# sb-mote2-oblong.net
KiCad netlist of a schematic drawn in EAGLE
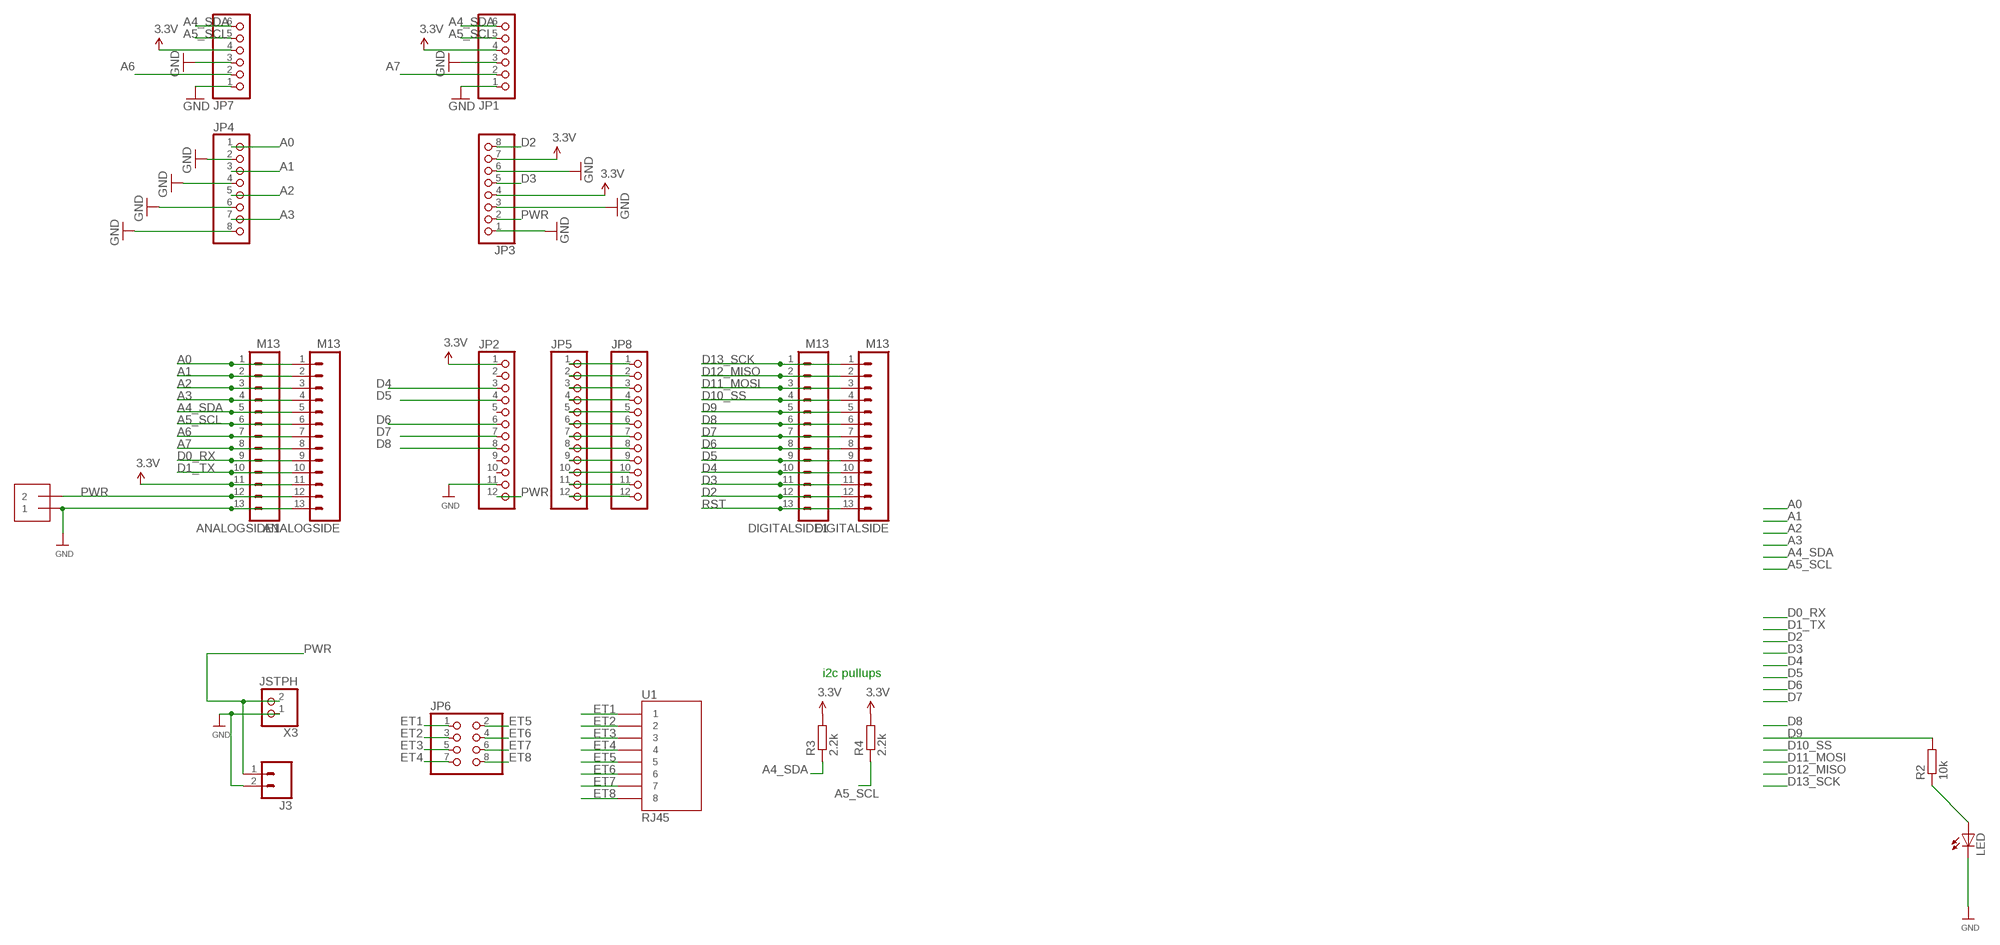
[diagram p0: schematic, sheet 1]

(export (version "E")
  (design (tool "Eeschema 10.0.6"))
  (components
    (comp (ref "ANALOGSIDE")
      (value "M13")
      (footprint "eagle-import:1X13")
      (libsource (lib "eagle-import") (part "M13"))
    )
    (comp (ref "ANALOGSIDE1")
      (value "M13")
      (footprint "eagle-import:1X13")
      (libsource (lib "eagle-import") (part "M13"))
    )
    (comp (ref "DIGITALSIDE")
      (value "M13")
      (footprint "eagle-import:1X13")
      (libsource (lib "eagle-import") (part "M13"))
    )
    (comp (ref "DIGITALSIDE1")
      (value "M13")
      (footprint "eagle-import:1X13")
      (libsource (lib "eagle-import") (part "M13"))
    )
    (comp (ref "J2")
      (value "1X2-3.5MM")
      (footprint "eagle-import:1X2-3.5MM")
      (libsource (lib "eagle-import") (part "1X2-3.5MM"))
    )
    (comp (ref "J3")
      (value "M02PTH")
      (footprint "eagle-import:1X02")
      (libsource (lib "eagle-import") (part "M02PTH"))
    )
    (comp (ref "JP1")
      (value "PINHD-1X6-3.5MM")
      (footprint "eagle-import:1X06-3.5MM")
      (libsource (lib "eagle-import") (part "PINHD-1X6-3.5MM"))
    )
    (comp (ref "JP2")
      (value "PINHD-1X12-CB")
      (footprint "eagle-import:1X12-CB")
      (libsource (lib "eagle-import") (part "PINHD-1X12-CB"))
    )
    (comp (ref "JP3")
      (value "PINHD-1X8-3.5MM")
      (footprint "eagle-import:1X08-3.5MM")
      (libsource (lib "eagle-import") (part "PINHD-1X8-3.5MM"))
    )
    (comp (ref "JP4")
      (value "PINHD-1X8-3.5MM")
      (footprint "eagle-import:1X08-3.5MM")
      (libsource (lib "eagle-import") (part "PINHD-1X8-3.5MM"))
    )
    (comp (ref "JP5")
      (value "PINHD-1X12-CB")
      (footprint "eagle-import:1X12-CB")
      (libsource (lib "eagle-import") (part "PINHD-1X12-CB"))
    )
    (comp (ref "JP6")
      (value "PINHD-2X4")
      (footprint "eagle-import:2X04")
      (libsource (lib "eagle-import") (part "PINHD-2X4"))
    )
    (comp (ref "JP7")
      (value "PINHD-1X6-3.5MM")
      (footprint "eagle-import:1X06-3.5MM")
      (libsource (lib "eagle-import") (part "PINHD-1X6-3.5MM"))
    )
    (comp (ref "JP8")
      (value "PINHD-1X12-CB")
      (footprint "eagle-import:1X12-CB")
      (libsource (lib "eagle-import") (part "PINHD-1X12-CB"))
    )
    (comp (ref "LED")
      (value "LED3MM")
      (footprint "eagle-import:LED3MM")
      (libsource (lib "eagle-import") (part "LED3MM"))
    )
    (comp (ref "R2")
      (value "10k")
      (footprint "eagle-import:0204_7")
      (libsource (lib "eagle-import") (part "R-EU_0204/7"))
    )
    (comp (ref "R3")
      (value "2.2k")
      (footprint "eagle-import:0204_7")
      (libsource (lib "eagle-import") (part "R-EU_0204/7"))
    )
    (comp (ref "R4")
      (value "2.2k")
      (footprint "eagle-import:0204_7")
      (libsource (lib "eagle-import") (part "R-EU_0204/7"))
    )
    (comp (ref "U1")
      (value "RJ45")
      (footprint "eagle-import:RJ45-8")
      (libsource (lib "eagle-import") (part "RJ45-8PTH"))
    )
    (comp (ref "X3")
      (value "JSTPH")
      (footprint "eagle-import:JSTPH2")
      (libsource (lib "eagle-import") (part "CON_JST_PH_2PIN"))
    )
  )
  (nets
    (net (code "1") (name "/A0") (class "Default")
      (node (ref "ANALOGSIDE") (pin "1") (pinfunction "1_1") (pintype "passive"))
      (node (ref "ANALOGSIDE1") (pin "1") (pinfunction "1_1") (pintype "passive"))
      (node (ref "JP4") (pin "1") (pinfunction "1_1") (pintype "passive"))
    )
    (net (code "2") (name "/A1") (class "Default")
      (node (ref "ANALOGSIDE") (pin "2") (pinfunction "2_2") (pintype "passive"))
      (node (ref "ANALOGSIDE1") (pin "2") (pinfunction "2_2") (pintype "passive"))
      (node (ref "JP4") (pin "3") (pinfunction "3_3") (pintype "passive"))
    )
    (net (code "3") (name "/A2") (class "Default")
      (node (ref "ANALOGSIDE") (pin "3") (pinfunction "3_3") (pintype "passive"))
      (node (ref "ANALOGSIDE1") (pin "3") (pinfunction "3_3") (pintype "passive"))
      (node (ref "JP4") (pin "5") (pinfunction "5_5") (pintype "passive"))
    )
    (net (code "4") (name "/A3") (class "Default")
      (node (ref "ANALOGSIDE") (pin "4") (pinfunction "4_4") (pintype "passive"))
      (node (ref "ANALOGSIDE1") (pin "4") (pinfunction "4_4") (pintype "passive"))
      (node (ref "JP4") (pin "7") (pinfunction "7_7") (pintype "passive"))
    )
    (net (code "5") (name "/A4_SDA") (class "Default")
      (node (ref "ANALOGSIDE") (pin "5") (pinfunction "5_5") (pintype "passive"))
      (node (ref "ANALOGSIDE1") (pin "5") (pinfunction "5_5") (pintype "passive"))
      (node (ref "JP1") (pin "6") (pinfunction "6_6") (pintype "passive"))
      (node (ref "JP7") (pin "6") (pinfunction "6_6") (pintype "passive"))
      (node (ref "R3") (pin "1") (pinfunction "1_1") (pintype "passive"))
    )
    (net (code "6") (name "/A5_SCL") (class "Default")
      (node (ref "ANALOGSIDE") (pin "6") (pinfunction "6_6") (pintype "passive"))
      (node (ref "ANALOGSIDE1") (pin "6") (pinfunction "6_6") (pintype "passive"))
      (node (ref "JP1") (pin "5") (pinfunction "5_5") (pintype "passive"))
      (node (ref "JP7") (pin "5") (pinfunction "5_5") (pintype "passive"))
      (node (ref "R4") (pin "1") (pinfunction "1_1") (pintype "passive"))
    )
    (net (code "7") (name "/A6") (class "Default")
      (node (ref "ANALOGSIDE") (pin "7") (pinfunction "7_7") (pintype "passive"))
      (node (ref "ANALOGSIDE1") (pin "7") (pinfunction "7_7") (pintype "passive"))
      (node (ref "JP7") (pin "2") (pinfunction "2_2") (pintype "passive"))
    )
    (net (code "8") (name "/A7") (class "Default")
      (node (ref "ANALOGSIDE") (pin "8") (pinfunction "8_8") (pintype "passive"))
      (node (ref "ANALOGSIDE1") (pin "8") (pinfunction "8_8") (pintype "passive"))
      (node (ref "JP1") (pin "2") (pinfunction "2_2") (pintype "passive"))
    )
    (net (code "9") (name "/D0_RX") (class "Default")
      (node (ref "ANALOGSIDE") (pin "9") (pinfunction "9_9") (pintype "passive"))
      (node (ref "ANALOGSIDE1") (pin "9") (pinfunction "9_9") (pintype "passive"))
    )
    (net (code "10") (name "/D1_TX") (class "Default")
      (node (ref "ANALOGSIDE") (pin "10") (pinfunction "10_10") (pintype "passive"))
      (node (ref "ANALOGSIDE1") (pin "10") (pinfunction "10_10") (pintype "passive"))
    )
    (net (code "11") (name "/D2") (class "Default")
      (node (ref "DIGITALSIDE") (pin "12") (pinfunction "12_12") (pintype "passive"))
      (node (ref "DIGITALSIDE1") (pin "12") (pinfunction "12_12") (pintype "passive"))
      (node (ref "JP3") (pin "8") (pinfunction "8_8") (pintype "passive"))
    )
    (net (code "12") (name "/D3") (class "Default")
      (node (ref "DIGITALSIDE") (pin "11") (pinfunction "11_11") (pintype "passive"))
      (node (ref "DIGITALSIDE1") (pin "11") (pinfunction "11_11") (pintype "passive"))
      (node (ref "JP3") (pin "5") (pinfunction "5_5") (pintype "passive"))
    )
    (net (code "13") (name "/D4") (class "Default")
      (node (ref "DIGITALSIDE") (pin "10") (pinfunction "10_10") (pintype "passive"))
      (node (ref "DIGITALSIDE1") (pin "10") (pinfunction "10_10") (pintype "passive"))
      (node (ref "JP2") (pin "3") (pinfunction "3_3") (pintype "passive"))
    )
    (net (code "14") (name "/D5") (class "Default")
      (node (ref "DIGITALSIDE") (pin "9") (pinfunction "9_9") (pintype "passive"))
      (node (ref "DIGITALSIDE1") (pin "9") (pinfunction "9_9") (pintype "passive"))
      (node (ref "JP2") (pin "4") (pinfunction "4_4") (pintype "passive"))
    )
    (net (code "15") (name "/D6") (class "Default")
      (node (ref "DIGITALSIDE") (pin "8") (pinfunction "8_8") (pintype "passive"))
      (node (ref "DIGITALSIDE1") (pin "8") (pinfunction "8_8") (pintype "passive"))
      (node (ref "JP2") (pin "6") (pinfunction "6_6") (pintype "passive"))
    )
    (net (code "16") (name "/D7") (class "Default")
      (node (ref "DIGITALSIDE") (pin "7") (pinfunction "7_7") (pintype "passive"))
      (node (ref "DIGITALSIDE1") (pin "7") (pinfunction "7_7") (pintype "passive"))
      (node (ref "JP2") (pin "7") (pinfunction "7_7") (pintype "passive"))
    )
    (net (code "17") (name "/D8") (class "Default")
      (node (ref "DIGITALSIDE") (pin "6") (pinfunction "6_6") (pintype "passive"))
      (node (ref "DIGITALSIDE1") (pin "6") (pinfunction "6_6") (pintype "passive"))
      (node (ref "JP2") (pin "8") (pinfunction "8_8") (pintype "passive"))
    )
    (net (code "18") (name "/D9") (class "Default")
      (node (ref "DIGITALSIDE") (pin "5") (pinfunction "5_5") (pintype "passive"))
      (node (ref "DIGITALSIDE1") (pin "5") (pinfunction "5_5") (pintype "passive"))
      (node (ref "R2") (pin "2") (pinfunction "2_2") (pintype "passive"))
    )
    (net (code "19") (name "/D10_SS") (class "Default")
      (node (ref "DIGITALSIDE") (pin "4") (pinfunction "4_4") (pintype "passive"))
      (node (ref "DIGITALSIDE1") (pin "4") (pinfunction "4_4") (pintype "passive"))
    )
    (net (code "20") (name "/D11_MOSI") (class "Default")
      (node (ref "DIGITALSIDE") (pin "3") (pinfunction "3_3") (pintype "passive"))
      (node (ref "DIGITALSIDE1") (pin "3") (pinfunction "3_3") (pintype "passive"))
    )
    (net (code "21") (name "/D12_MISO") (class "Default")
      (node (ref "DIGITALSIDE") (pin "2") (pinfunction "2_2") (pintype "passive"))
      (node (ref "DIGITALSIDE1") (pin "2") (pinfunction "2_2") (pintype "passive"))
    )
    (net (code "22") (name "/D13_SCK") (class "Default")
      (node (ref "DIGITALSIDE") (pin "1") (pinfunction "1_1") (pintype "passive"))
      (node (ref "DIGITALSIDE1") (pin "1") (pinfunction "1_1") (pintype "passive"))
    )
    (net (code "23") (name "/ET1") (class "Default")
      (node (ref "JP6") (pin "1") (pinfunction "1_1") (pintype "passive"))
      (node (ref "U1") (pin "1") (pinfunction "1_1") (pintype "bidirectional"))
    )
    (net (code "24") (name "/ET2") (class "Default")
      (node (ref "JP6") (pin "3") (pinfunction "3_3") (pintype "passive"))
      (node (ref "U1") (pin "2") (pinfunction "2_2") (pintype "bidirectional"))
    )
    (net (code "25") (name "/ET3") (class "Default")
      (node (ref "JP6") (pin "5") (pinfunction "5_5") (pintype "passive"))
      (node (ref "U1") (pin "3") (pinfunction "3_3") (pintype "bidirectional"))
    )
    (net (code "26") (name "/ET4") (class "Default")
      (node (ref "JP6") (pin "7") (pinfunction "7_7") (pintype "passive"))
      (node (ref "U1") (pin "4") (pinfunction "4_4") (pintype "bidirectional"))
    )
    (net (code "27") (name "/ET5") (class "Default")
      (node (ref "JP6") (pin "2") (pinfunction "2_2") (pintype "passive"))
      (node (ref "U1") (pin "5") (pinfunction "5_5") (pintype "bidirectional"))
    )
    (net (code "28") (name "/ET6") (class "Default")
      (node (ref "JP6") (pin "4") (pinfunction "4_4") (pintype "passive"))
      (node (ref "U1") (pin "6") (pinfunction "6_6") (pintype "bidirectional"))
    )
    (net (code "29") (name "/ET7") (class "Default")
      (node (ref "JP6") (pin "6") (pinfunction "6_6") (pintype "passive"))
      (node (ref "U1") (pin "7") (pinfunction "7_7") (pintype "bidirectional"))
    )
    (net (code "30") (name "/ET8") (class "Default")
      (node (ref "JP6") (pin "8") (pinfunction "8_8") (pintype "passive"))
      (node (ref "U1") (pin "8") (pinfunction "8_8") (pintype "bidirectional"))
    )
    (net (code "31") (name "/PWR") (class "Default")
      (node (ref "ANALOGSIDE") (pin "12") (pinfunction "12_12") (pintype "passive"))
      (node (ref "ANALOGSIDE1") (pin "12") (pinfunction "12_12") (pintype "passive"))
      (node (ref "J2") (pin "2") (pinfunction "2_2") (pintype "passive"))
      (node (ref "J3") (pin "1") (pinfunction "1_1") (pintype "passive"))
      (node (ref "JP2") (pin "12") (pinfunction "12_12") (pintype "passive"))
      (node (ref "JP3") (pin "2") (pinfunction "2_2") (pintype "passive"))
      (node (ref "X3") (pin "2") (pinfunction "2_2") (pintype "passive"))
    )
    (net (code "32") (name "/RST") (class "Default")
      (node (ref "DIGITALSIDE") (pin "13") (pinfunction "13_13") (pintype "passive"))
      (node (ref "DIGITALSIDE1") (pin "13") (pinfunction "13_13") (pintype "passive"))
    )
    (net (code "33") (name "3.3V") (class "Default")
      (node (ref "ANALOGSIDE") (pin "11") (pinfunction "11_11") (pintype "passive"))
      (node (ref "ANALOGSIDE1") (pin "11") (pinfunction "11_11") (pintype "passive"))
      (node (ref "JP1") (pin "4") (pinfunction "4_4") (pintype "passive"))
      (node (ref "JP2") (pin "1") (pinfunction "1_1") (pintype "passive"))
      (node (ref "JP3") (pin "4") (pinfunction "4_4") (pintype "passive"))
      (node (ref "JP3") (pin "7") (pinfunction "7_7") (pintype "passive"))
      (node (ref "JP7") (pin "4") (pinfunction "4_4") (pintype "passive"))
      (node (ref "R3") (pin "2") (pinfunction "2_2") (pintype "passive"))
      (node (ref "R4") (pin "2") (pinfunction "2_2") (pintype "passive"))
    )
    (net (code "34") (name "GND") (class "Default")
      (node (ref "ANALOGSIDE") (pin "13") (pinfunction "13_13") (pintype "passive"))
      (node (ref "ANALOGSIDE1") (pin "13") (pinfunction "13_13") (pintype "passive"))
      (node (ref "J2") (pin "1") (pinfunction "1_1") (pintype "passive"))
      (node (ref "J3") (pin "2") (pinfunction "2_2") (pintype "passive"))
      (node (ref "JP1") (pin "1") (pinfunction "1_1") (pintype "passive"))
      (node (ref "JP1") (pin "3") (pinfunction "3_3") (pintype "passive"))
      (node (ref "JP2") (pin "11") (pinfunction "11_11") (pintype "passive"))
      (node (ref "JP3") (pin "1") (pinfunction "1_1") (pintype "passive"))
      (node (ref "JP3") (pin "3") (pinfunction "3_3") (pintype "passive"))
      (node (ref "JP3") (pin "6") (pinfunction "6_6") (pintype "passive"))
      (node (ref "JP4") (pin "2") (pinfunction "2_2") (pintype "passive"))
      (node (ref "JP4") (pin "4") (pinfunction "4_4") (pintype "passive"))
      (node (ref "JP4") (pin "6") (pinfunction "6_6") (pintype "passive"))
      (node (ref "JP4") (pin "8") (pinfunction "8_8") (pintype "passive"))
      (node (ref "JP7") (pin "1") (pinfunction "1_1") (pintype "passive"))
      (node (ref "JP7") (pin "3") (pinfunction "3_3") (pintype "passive"))
      (node (ref "LED") (pin "K") (pinfunction "C_K") (pintype "passive"))
      (node (ref "X3") (pin "1") (pinfunction "1_1") (pintype "passive"))
    )
    (net (code "35") (name "Net-(JP5-Pad1)") (class "Default")
      (node (ref "JP5") (pin "1") (pinfunction "1_1") (pintype "passive"))
      (node (ref "JP8") (pin "1") (pinfunction "1_1") (pintype "passive"))
    )
    (net (code "36") (name "Net-(JP5-Pad2)") (class "Default")
      (node (ref "JP5") (pin "2") (pinfunction "2_2") (pintype "passive"))
      (node (ref "JP8") (pin "2") (pinfunction "2_2") (pintype "passive"))
    )
    (net (code "37") (name "Net-(JP5-Pad3)") (class "Default")
      (node (ref "JP5") (pin "3") (pinfunction "3_3") (pintype "passive"))
      (node (ref "JP8") (pin "3") (pinfunction "3_3") (pintype "passive"))
    )
    (net (code "38") (name "Net-(JP5-Pad4)") (class "Default")
      (node (ref "JP5") (pin "4") (pinfunction "4_4") (pintype "passive"))
      (node (ref "JP8") (pin "4") (pinfunction "4_4") (pintype "passive"))
    )
    (net (code "39") (name "Net-(JP5-Pad5)") (class "Default")
      (node (ref "JP5") (pin "5") (pinfunction "5_5") (pintype "passive"))
      (node (ref "JP8") (pin "5") (pinfunction "5_5") (pintype "passive"))
    )
    (net (code "40") (name "Net-(JP5-Pad6)") (class "Default")
      (node (ref "JP5") (pin "6") (pinfunction "6_6") (pintype "passive"))
      (node (ref "JP8") (pin "6") (pinfunction "6_6") (pintype "passive"))
    )
    (net (code "41") (name "Net-(JP5-Pad7)") (class "Default")
      (node (ref "JP5") (pin "7") (pinfunction "7_7") (pintype "passive"))
      (node (ref "JP8") (pin "7") (pinfunction "7_7") (pintype "passive"))
    )
    (net (code "42") (name "Net-(JP5-Pad8)") (class "Default")
      (node (ref "JP5") (pin "8") (pinfunction "8_8") (pintype "passive"))
      (node (ref "JP8") (pin "8") (pinfunction "8_8") (pintype "passive"))
    )
    (net (code "43") (name "Net-(JP5-Pad9)") (class "Default")
      (node (ref "JP5") (pin "9") (pinfunction "9_9") (pintype "passive"))
      (node (ref "JP8") (pin "9") (pinfunction "9_9") (pintype "passive"))
    )
    (net (code "44") (name "Net-(JP5-Pad10)") (class "Default")
      (node (ref "JP5") (pin "10") (pinfunction "10_10") (pintype "passive"))
      (node (ref "JP8") (pin "10") (pinfunction "10_10") (pintype "passive"))
    )
    (net (code "45") (name "Net-(JP5-Pad11)") (class "Default")
      (node (ref "JP5") (pin "11") (pinfunction "11_11") (pintype "passive"))
      (node (ref "JP8") (pin "11") (pinfunction "11_11") (pintype "passive"))
    )
    (net (code "46") (name "Net-(JP5-Pad12)") (class "Default")
      (node (ref "JP5") (pin "12") (pinfunction "12_12") (pintype "passive"))
      (node (ref "JP8") (pin "12") (pinfunction "12_12") (pintype "passive"))
    )
    (net (code "47") (name "Net-(LED-PadA)") (class "Default")
      (node (ref "LED") (pin "A") (pinfunction "A_A") (pintype "passive"))
      (node (ref "R2") (pin "1") (pinfunction "1_1") (pintype "passive"))
    )
    (net (code "48") (name "unconnected-(JP2-Pad2)") (class "Default")
      (node (ref "JP2") (pin "2") (pinfunction "2_2") (pintype "passive"))
    )
    (net (code "49") (name "unconnected-(JP2-Pad5)") (class "Default")
      (node (ref "JP2") (pin "5") (pinfunction "5_5") (pintype "passive"))
    )
    (net (code "50") (name "unconnected-(JP2-Pad9)") (class "Default")
      (node (ref "JP2") (pin "9") (pinfunction "9_9") (pintype "passive"))
    )
    (net (code "51") (name "unconnected-(JP2-Pad10)") (class "Default")
      (node (ref "JP2") (pin "10") (pinfunction "10_10") (pintype "passive"))
    )
  )
)
